# LockSequencer.net
KiCad netlist of a schematic drawn in EAGLE
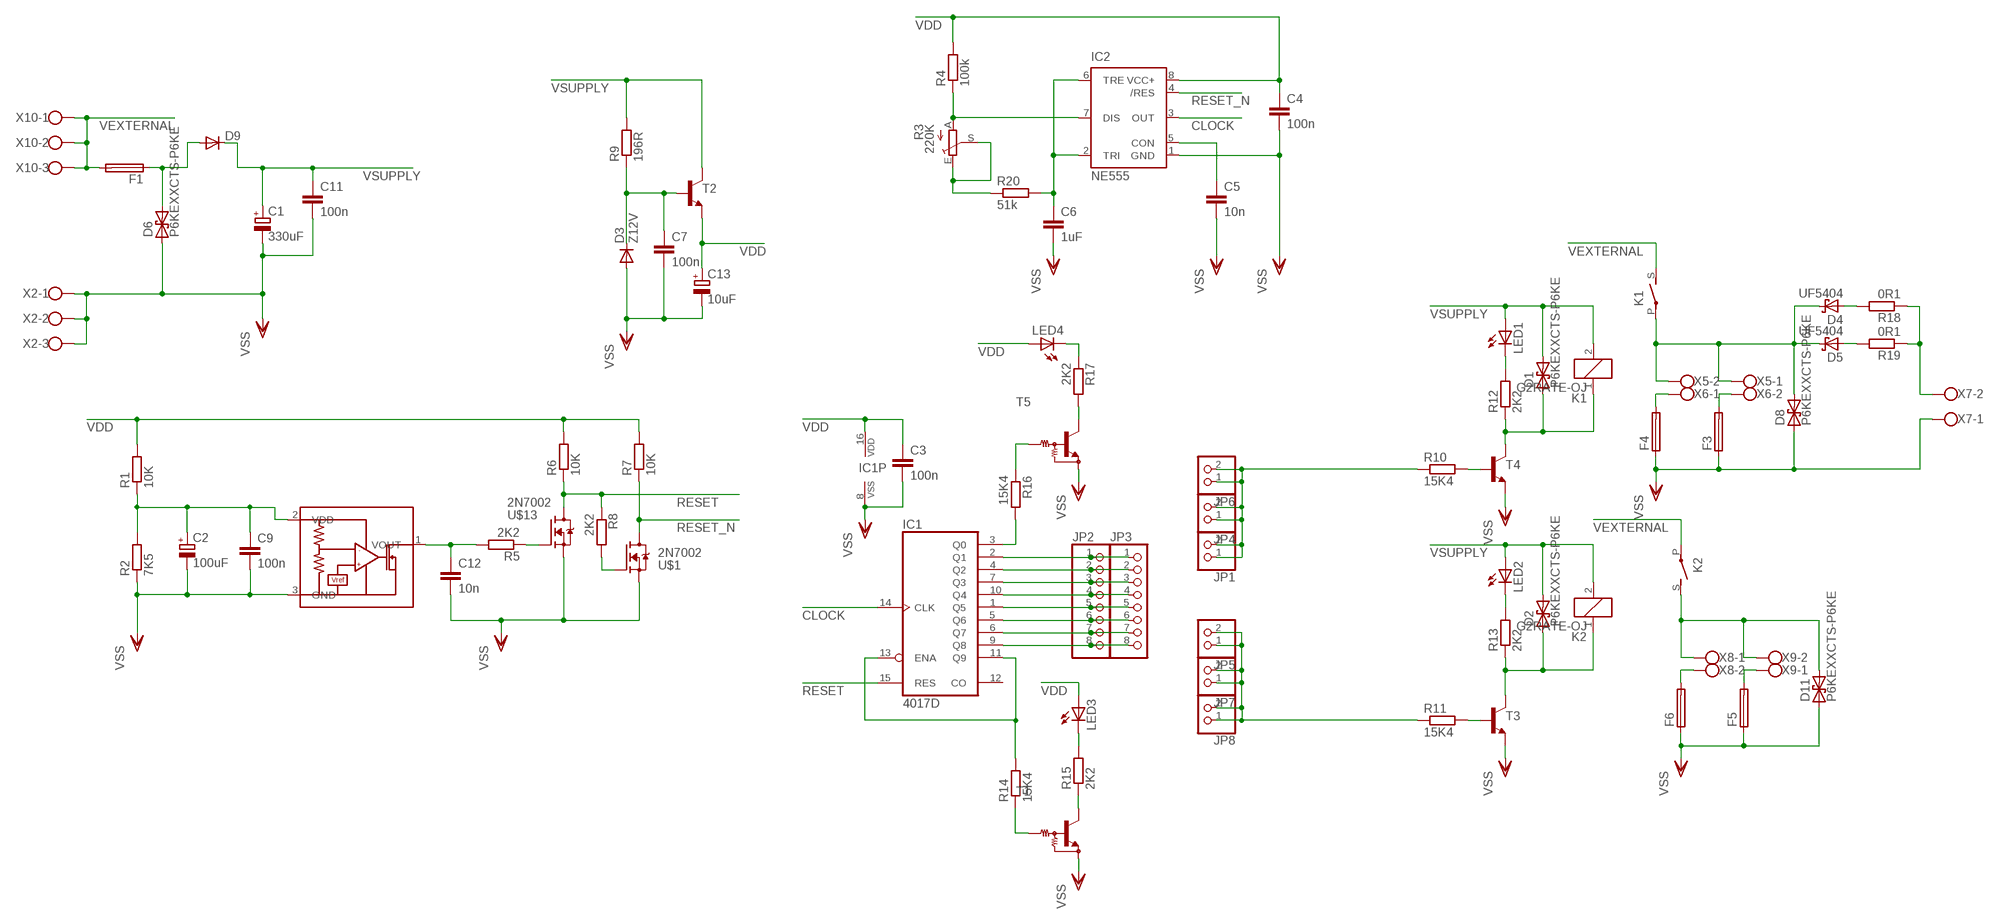
[diagram p0: schematic, sheet 1]

(export (version "E")
  (design (tool "Eeschema 10.0.6"))
  (components
    (comp (ref "C1")
      (value "330uF")
      (footprint "eagle-import:E3,5-8")
      (libsource (lib "eagle-import") (part "CPOL-EUE3.5-8"))
    )
    (comp (ref "C2")
      (value "100uF")
      (footprint "eagle-import:E2-5")
      (libsource (lib "eagle-import") (part "CPOL-EUE2-5"))
    )
    (comp (ref "C3")
      (value "100n")
      (footprint "eagle-import:C1206K")
      (libsource (lib "eagle-import") (part "C-EUC1206K"))
    )
    (comp (ref "C4")
      (value "100n")
      (footprint "eagle-import:C050-024X044")
      (libsource (lib "eagle-import") (part "C-EU050-024X044"))
    )
    (comp (ref "C5")
      (value "10n")
      (footprint "eagle-import:C1206K")
      (libsource (lib "eagle-import") (part "C-EUC1206K"))
    )
    (comp (ref "C6")
      (value "1uF")
      (footprint "eagle-import:C1206K")
      (libsource (lib "eagle-import") (part "C-EUC1206K"))
    )
    (comp (ref "C7")
      (value "100n")
      (footprint "eagle-import:C1206K")
      (libsource (lib "eagle-import") (part "C-EUC1206K"))
    )
    (comp (ref "C9")
      (value "100n")
      (footprint "eagle-import:C1206K")
      (libsource (lib "eagle-import") (part "C-EUC1206K"))
    )
    (comp (ref "C11")
      (value "100n")
      (footprint "eagle-import:C050-024X044")
      (libsource (lib "eagle-import") (part "C-EU050-024X044"))
    )
    (comp (ref "C12")
      (value "10n")
      (footprint "eagle-import:C1206K")
      (libsource (lib "eagle-import") (part "C-EUC1206K"))
    )
    (comp (ref "C13")
      (value "10uF")
      (footprint "eagle-import:E2-5")
      (libsource (lib "eagle-import") (part "CPOL-EUE2-5"))
    )
    (comp (ref "D1")
      (value "P6KEXXCTS-P6KE")
      (footprint "eagle-import:DO15-10")
      (libsource (lib "eagle-import") (part "P6KEXXCTS-P6KE"))
    )
    (comp (ref "D2")
      (value "P6KEXXCTS-P6KE")
      (footprint "eagle-import:DO15-10")
      (libsource (lib "eagle-import") (part "P6KEXXCTS-P6KE"))
    )
    (comp (ref "D3")
      (value "Z12V")
      (footprint "eagle-import:SOD323-W")
      (libsource (lib "eagle-import") (part "DIODE-SOD323-W"))
    )
    (comp (ref "D4")
      (value "UF5404")
      (footprint "eagle-import:CB429-15R")
      (libsource (lib "eagle-import") (part "SCHOTTKY-DIODECB429-15VR"))
    )
    (comp (ref "D5")
      (value "UF5404")
      (footprint "eagle-import:CB429-15V")
      (libsource (lib "eagle-import") (part "SCHOTTKY-DIODECB429-15V"))
    )
    (comp (ref "D6")
      (value "P6KEXXCTS-P6KE")
      (footprint "eagle-import:DO15-10")
      (libsource (lib "eagle-import") (part "P6KEXXCTS-P6KE"))
    )
    (comp (ref "D8")
      (value "P6KEXXCTS-P6KE")
      (footprint "eagle-import:DO15-10")
      (libsource (lib "eagle-import") (part "P6KEXXCTS-P6KE"))
    )
    (comp (ref "D9")
      (value "DIODE-SOD123")
      (footprint "eagle-import:SOD123")
      (libsource (lib "eagle-import") (part "DIODE-SOD123"))
    )
    (comp (ref "D11")
      (value "P6KEXXCTS-P6KE")
      (footprint "eagle-import:DO15-10")
      (libsource (lib "eagle-import") (part "P6KEXXCTS-P6KE"))
    )
    (comp (ref "F1")
      (value "TE5")
      (footprint "eagle-import:TE5")
      (libsource (lib "eagle-import") (part "TE5"))
    )
    (comp (ref "F3")
      (value "TE5")
      (footprint "eagle-import:TE5")
      (libsource (lib "eagle-import") (part "TE5"))
    )
    (comp (ref "F4")
      (value "TE5")
      (footprint "eagle-import:TE5")
      (libsource (lib "eagle-import") (part "TE5"))
    )
    (comp (ref "F5")
      (value "TE5")
      (footprint "eagle-import:TE5")
      (libsource (lib "eagle-import") (part "TE5"))
    )
    (comp (ref "F6")
      (value "TE5")
      (footprint "eagle-import:TE5")
      (libsource (lib "eagle-import") (part "TE5"))
    )
    (comp (ref "IC1")
      (value "4017D")
      (footprint "eagle-import:SO16")
      (libsource (lib "eagle-import") (part "4017D"))
    )
    (comp (ref "IC2")
      (value "NE555")
      (footprint "eagle-import:DIL-08")
      (fields (field (name "MF") "Arrow Electronics") (field (name "MPN") "NE555N"))
      (libsource (lib "eagle-import") (part "NE555"))
    )
    (comp (ref "JP1")
      (value "PINHD-1X2")
      (footprint "eagle-import:1X02")
      (libsource (lib "eagle-import") (part "PINHD-1X2"))
    )
    (comp (ref "JP2")
      (value "PINHD-1X8")
      (footprint "eagle-import:1X08")
      (libsource (lib "eagle-import") (part "PINHD-1X8"))
    )
    (comp (ref "JP3")
      (value "PINHD-1X8")
      (footprint "eagle-import:1X08")
      (libsource (lib "eagle-import") (part "PINHD-1X8"))
    )
    (comp (ref "JP4")
      (value "PINHD-1X2")
      (footprint "eagle-import:1X02")
      (libsource (lib "eagle-import") (part "PINHD-1X2"))
    )
    (comp (ref "JP5")
      (value "PINHD-1X2")
      (footprint "eagle-import:1X02")
      (libsource (lib "eagle-import") (part "PINHD-1X2"))
    )
    (comp (ref "JP6")
      (value "PINHD-1X2")
      (footprint "eagle-import:1X02")
      (libsource (lib "eagle-import") (part "PINHD-1X2"))
    )
    (comp (ref "JP7")
      (value "PINHD-1X2")
      (footprint "eagle-import:1X02")
      (libsource (lib "eagle-import") (part "PINHD-1X2"))
    )
    (comp (ref "JP8")
      (value "PINHD-1X2")
      (footprint "eagle-import:1X02")
      (libsource (lib "eagle-import") (part "PINHD-1X2"))
    )
    (comp (ref "K1")
      (value "G2RATE-OJ")
      (footprint "eagle-import:G2RA-SHORTER")
      (libsource (lib "eagle-import") (part "G2RATE-OJ"))
    )
    (comp (ref "K2")
      (value "G2RATE-OJ")
      (footprint "eagle-import:G2RA-SHORTER")
      (libsource (lib "eagle-import") (part "G2RATE-OJ"))
    )
    (comp (ref "LED1")
      (value "LED5MM")
      (footprint "eagle-import:LED5MM")
      (libsource (lib "eagle-import") (part "LED5MM"))
    )
    (comp (ref "LED2")
      (value "LED5MM")
      (footprint "eagle-import:LED5MM")
      (libsource (lib "eagle-import") (part "LED5MM"))
    )
    (comp (ref "LED3")
      (value "LED5MM")
      (footprint "eagle-import:LED5MM")
      (libsource (lib "eagle-import") (part "LED5MM"))
    )
    (comp (ref "LED4")
      (value "LED5MM")
      (footprint "eagle-import:LED5MM")
      (libsource (lib "eagle-import") (part "LED5MM"))
    )
    (comp (ref "R1")
      (value "10K")
      (footprint "eagle-import:0207_7")
      (libsource (lib "eagle-import") (part "R-EU_0207/7"))
    )
    (comp (ref "R2")
      (value "7K5")
      (footprint "eagle-import:0207_7")
      (libsource (lib "eagle-import") (part "R-EU_0207/7"))
    )
    (comp (ref "R3")
      (value "220K")
      (footprint "eagle-import:CA9V")
      (libsource (lib "eagle-import") (part "TRIM_EU-CA9V"))
    )
    (comp (ref "R4")
      (value "100k")
      (footprint "eagle-import:0207_7")
      (libsource (lib "eagle-import") (part "R-EU_0207/7"))
    )
    (comp (ref "R5")
      (value "2K2")
      (footprint "eagle-import:R0402")
      (libsource (lib "eagle-import") (part "R-EU_R0402"))
    )
    (comp (ref "R6")
      (value "10K")
      (footprint "eagle-import:0207_7")
      (libsource (lib "eagle-import") (part "R-EU_0207/7"))
    )
    (comp (ref "R7")
      (value "10K")
      (footprint "eagle-import:R0805")
      (libsource (lib "eagle-import") (part "R-EU_R0805"))
    )
    (comp (ref "R8")
      (value "2K2")
      (footprint "eagle-import:0207_7")
      (libsource (lib "eagle-import") (part "R-EU_0207/7"))
    )
    (comp (ref "R9")
      (value "196R")
      (footprint "eagle-import:R0805")
      (libsource (lib "eagle-import") (part "R-EU_R0805"))
    )
    (comp (ref "R10")
      (value "15K4")
      (footprint "eagle-import:R0603")
      (libsource (lib "eagle-import") (part "R-EU_R0603"))
    )
    (comp (ref "R11")
      (value "15K4")
      (footprint "eagle-import:R0603")
      (libsource (lib "eagle-import") (part "R-EU_R0603"))
    )
    (comp (ref "R12")
      (value "2K2")
      (footprint "eagle-import:0207_7")
      (libsource (lib "eagle-import") (part "R-EU_0207/7"))
    )
    (comp (ref "R13")
      (value "2K2")
      (footprint "eagle-import:0207_7")
      (libsource (lib "eagle-import") (part "R-EU_0207/7"))
    )
    (comp (ref "R14")
      (value "15K4")
      (footprint "eagle-import:R0603")
      (libsource (lib "eagle-import") (part "R-EU_R0603"))
    )
    (comp (ref "R15")
      (value "2K2")
      (footprint "eagle-import:0207_7")
      (libsource (lib "eagle-import") (part "R-EU_0207/7"))
    )
    (comp (ref "R16")
      (value "15K4")
      (footprint "eagle-import:R0603")
      (libsource (lib "eagle-import") (part "R-EU_R0603"))
    )
    (comp (ref "R17")
      (value "2K2")
      (footprint "eagle-import:0207_7")
      (libsource (lib "eagle-import") (part "R-EU_0207/7"))
    )
    (comp (ref "R18")
      (value "0R1")
      (footprint "eagle-import:R2512")
      (libsource (lib "eagle-import") (part "R-EU_R2512"))
    )
    (comp (ref "R19")
      (value "0R1")
      (footprint "eagle-import:R2512")
      (libsource (lib "eagle-import") (part "R-EU_R2512"))
    )
    (comp (ref "R20")
      (value "51k")
      (footprint "eagle-import:0207_7")
      (libsource (lib "eagle-import") (part "R-EU_0207/7"))
    )
    (comp (ref "T1")
      (value "-NPN_DRIVER-")
      (footprint "eagle-import:SOT23")
      (libsource (lib "eagle-import") (part "-NPN_DRIVER-"))
    )
    (comp (ref "T2")
      (value "MMBTA42LT1-NPN-SOT23-BEC")
      (footprint "eagle-import:SOT23-BEC")
      (libsource (lib "eagle-import") (part "-NPN-SOT23-BECMMBTA42LT1"))
    )
    (comp (ref "T3")
      (value "MMBTA42LT1-NPN-SOT23-BEC")
      (footprint "eagle-import:SOT23-BEC")
      (libsource (lib "eagle-import") (part "-NPN-SOT23-BECMMBTA42LT1"))
    )
    (comp (ref "T4")
      (value "MMBTA42LT1-NPN-SOT23-BEC")
      (footprint "eagle-import:SOT23-BEC")
      (libsource (lib "eagle-import") (part "-NPN-SOT23-BECMMBTA42LT1"))
    )
    (comp (ref "T5")
      (value "-NPN_DRIVER-")
      (footprint "eagle-import:SOT23")
      (libsource (lib "eagle-import") (part "-NPN_DRIVER-"))
    )
    (comp (ref "U$1")
      (value "2N7002")
      (footprint "eagle-import:SOT23")
      (libsource (lib "eagle-import") (part "2N7002"))
    )
    (comp (ref "U$4")
      (value "BU48XXG")
      (footprint "eagle-import:SOT95P280X125-5N")
      (libsource (lib "eagle-import") (part "BU48XXG"))
    )
    (comp (ref "U$13")
      (value "2N7002")
      (footprint "eagle-import:SOT23")
      (libsource (lib "eagle-import") (part "2N7002"))
    )
    (comp (ref "X2")
      (value "W237-103")
      (footprint "eagle-import:W237-103")
      (fields (field (name "MPN") "237-103"))
      (libsource (lib "eagle-import") (part "W237-103"))
    )
    (comp (ref "X5")
      (value "W237-102")
      (footprint "eagle-import:W237-102")
      (fields (field (name "MPN") "237-102"))
      (libsource (lib "eagle-import") (part "W237-102"))
    )
    (comp (ref "X6")
      (value "W237-102")
      (footprint "eagle-import:W237-102")
      (fields (field (name "MPN") "237-102"))
      (libsource (lib "eagle-import") (part "W237-102"))
    )
    (comp (ref "X7")
      (value "W237-102")
      (footprint "eagle-import:W237-102")
      (fields (field (name "MPN") "237-102"))
      (libsource (lib "eagle-import") (part "W237-102"))
    )
    (comp (ref "X8")
      (value "W237-102")
      (footprint "eagle-import:W237-102")
      (fields (field (name "MPN") "237-102"))
      (libsource (lib "eagle-import") (part "W237-102"))
    )
    (comp (ref "X9")
      (value "W237-102")
      (footprint "eagle-import:W237-102")
      (fields (field (name "MPN") "237-102"))
      (libsource (lib "eagle-import") (part "W237-102"))
    )
    (comp (ref "X10")
      (value "W237-103")
      (footprint "eagle-import:W237-103")
      (fields (field (name "MPN") "237-103"))
      (libsource (lib "eagle-import") (part "W237-103"))
    )
  )
  (nets
    (net (code "1") (name "/CLOCK") (class "Default")
      (node (ref "IC1") (pin "14") (pinfunction "CLK_14") (pintype "input"))
      (node (ref "IC2") (pin "3") (pinfunction "OUT_3") (pintype "output"))
    )
    (net (code "2") (name "/RESET") (class "Default")
      (node (ref "IC1") (pin "15") (pinfunction "RES_15") (pintype "input"))
      (node (ref "R6") (pin "1") (pinfunction "1_1") (pintype "passive"))
      (node (ref "R8") (pin "1") (pinfunction "1_1") (pintype "passive"))
      (node (ref "U$13") (pin "3") (pinfunction "D_3") (pintype "passive"))
    )
    (net (code "3") (name "/RESET_N") (class "Default")
      (node (ref "IC2") (pin "4") (pinfunction "/RES_4") (pintype "input"))
      (node (ref "R7") (pin "1") (pinfunction "1_1") (pintype "passive"))
      (node (ref "U$1") (pin "3") (pinfunction "D_3") (pintype "passive"))
    )
    (net (code "4") (name "/VDD") (class "Default")
      (node (ref "C13") (pin "+") (pinfunction "+_+") (pintype "passive"))
      (node (ref "C3") (pin "1") (pinfunction "1_1") (pintype "passive"))
      (node (ref "C4") (pin "1") (pinfunction "1_1") (pintype "passive"))
      (node (ref "IC1") (pin "16") (pinfunction "VDD_16") (pintype "power_in"))
      (node (ref "IC2") (pin "8") (pinfunction "VCC+_8") (pintype "power_in"))
      (node (ref "LED3") (pin "A") (pinfunction "A_A") (pintype "passive"))
      (node (ref "LED4") (pin "A") (pinfunction "A_A") (pintype "passive"))
      (node (ref "R1") (pin "2") (pinfunction "2_2") (pintype "passive"))
      (node (ref "R4") (pin "2") (pinfunction "2_2") (pintype "passive"))
      (node (ref "R6") (pin "2") (pinfunction "2_2") (pintype "passive"))
      (node (ref "R7") (pin "2") (pinfunction "2_2") (pintype "passive"))
      (node (ref "T2") (pin "E") (pinfunction "E_E") (pintype "passive"))
    )
    (net (code "5") (name "/VEXTERNAL") (class "Default")
      (node (ref "F1") (pin "2") (pinfunction "2_2") (pintype "passive"))
      (node (ref "K1") (pin "S") (pinfunction "S_S") (pintype "passive"))
      (node (ref "K2") (pin "P") (pinfunction "P_P") (pintype "passive"))
      (node (ref "X10") (pin "1") (pinfunction "KL_1") (pintype "passive"))
      (node (ref "X10") (pin "2") (pinfunction "KL_2") (pintype "passive"))
      (node (ref "X10") (pin "3") (pinfunction "KL_3") (pintype "passive"))
    )
    (net (code "6") (name "/VSUPPLY") (class "Default")
      (node (ref "C1") (pin "+") (pinfunction "+_+") (pintype "passive"))
      (node (ref "C11") (pin "1") (pinfunction "1_1") (pintype "passive"))
      (node (ref "D1") (pin "C") (pinfunction "2_C") (pintype "passive"))
      (node (ref "D2") (pin "C") (pinfunction "2_C") (pintype "passive"))
      (node (ref "D9") (pin "C") (pinfunction "C_C") (pintype "passive"))
      (node (ref "K1") (pin "2") (pinfunction "2_2") (pintype "passive"))
      (node (ref "K2") (pin "2") (pinfunction "2_2") (pintype "passive"))
      (node (ref "LED1") (pin "A") (pinfunction "A_A") (pintype "passive"))
      (node (ref "LED2") (pin "A") (pinfunction "A_A") (pintype "passive"))
      (node (ref "R9") (pin "2") (pinfunction "2_2") (pintype "passive"))
      (node (ref "T2") (pin "C") (pinfunction "C_C") (pintype "passive"))
    )
    (net (code "7") (name "Net-(C7-Pad1)") (class "Default")
      (node (ref "C7") (pin "1") (pinfunction "1_1") (pintype "passive"))
      (node (ref "D3") (pin "C") (pinfunction "C_C") (pintype "passive"))
      (node (ref "R9") (pin "1") (pinfunction "1_1") (pintype "passive"))
      (node (ref "T2") (pin "B") (pinfunction "B_B") (pintype "passive"))
    )
    (net (code "8") (name "Net-(D1-1)") (class "Default")
      (node (ref "D1") (pin "A") (pinfunction "1_A") (pintype "passive"))
      (node (ref "K1") (pin "1") (pinfunction "1_1") (pintype "passive"))
      (node (ref "R12") (pin "1") (pinfunction "1_1") (pintype "passive"))
      (node (ref "T4") (pin "C") (pinfunction "C_C") (pintype "passive"))
    )
    (net (code "9") (name "Net-(D2-1)") (class "Default")
      (node (ref "D2") (pin "A") (pinfunction "1_A") (pintype "passive"))
      (node (ref "K2") (pin "1") (pinfunction "1_1") (pintype "passive"))
      (node (ref "R13") (pin "1") (pinfunction "1_1") (pintype "passive"))
      (node (ref "T3") (pin "C") (pinfunction "C_C") (pintype "passive"))
    )
    (net (code "10") (name "Net-(D4-PadA)") (class "Default")
      (node (ref "D4") (pin "A") (pinfunction "A_A") (pintype "passive"))
      (node (ref "R18") (pin "2") (pinfunction "2_2") (pintype "passive"))
    )
    (net (code "11") (name "Net-(D5-PadA)") (class "Default")
      (node (ref "D5") (pin "A") (pinfunction "A_A") (pintype "passive"))
      (node (ref "R19") (pin "2") (pinfunction "2_2") (pintype "passive"))
    )
    (net (code "12") (name "Net-(D6-2)") (class "Default")
      (node (ref "D6") (pin "C") (pinfunction "2_C") (pintype "passive"))
      (node (ref "D9") (pin "A") (pinfunction "A_A") (pintype "passive"))
      (node (ref "F1") (pin "1") (pinfunction "1_1") (pintype "passive"))
    )
    (net (code "13") (name "Net-(D8-2)") (class "Default")
      (node (ref "D4") (pin "C") (pinfunction "C_C") (pintype "passive"))
      (node (ref "D5") (pin "C") (pinfunction "C_C") (pintype "passive"))
      (node (ref "D8") (pin "C") (pinfunction "2_C") (pintype "passive"))
      (node (ref "K1") (pin "P") (pinfunction "P_P") (pintype "passive"))
      (node (ref "X5") (pin "1") (pinfunction "KL_1") (pintype "passive"))
      (node (ref "X5") (pin "2") (pinfunction "KL_2") (pintype "passive"))
    )
    (net (code "14") (name "Net-(D11-2)") (class "Default")
      (node (ref "D11") (pin "C") (pinfunction "2_C") (pintype "passive"))
      (node (ref "K2") (pin "S") (pinfunction "S_S") (pintype "passive"))
      (node (ref "X8") (pin "1") (pinfunction "KL_1") (pintype "passive"))
      (node (ref "X9") (pin "2") (pinfunction "KL_2") (pintype "passive"))
    )
    (net (code "15") (name "Net-(IC1A-ENA)") (class "Default")
      (node (ref "IC1") (pin "11") (pinfunction "Q9_11") (pintype "output"))
      (node (ref "IC1") (pin "13") (pinfunction "ENA_13") (pintype "input"))
      (node (ref "R14") (pin "2") (pinfunction "2_2") (pintype "passive"))
    )
    (net (code "16") (name "Net-(IC1A-Q0)") (class "Default")
      (node (ref "IC1") (pin "3") (pinfunction "Q0_3") (pintype "output"))
      (node (ref "R16") (pin "2") (pinfunction "2_2") (pintype "passive"))
    )
    (net (code "17") (name "Net-(IC1A-Q1)") (class "Default")
      (node (ref "IC1") (pin "2") (pinfunction "Q1_2") (pintype "output"))
      (node (ref "JP2") (pin "1") (pinfunction "1_1") (pintype "passive"))
      (node (ref "JP3") (pin "1") (pinfunction "1_1") (pintype "passive"))
    )
    (net (code "18") (name "Net-(IC1A-Q2)") (class "Default")
      (node (ref "IC1") (pin "4") (pinfunction "Q2_4") (pintype "output"))
      (node (ref "JP2") (pin "2") (pinfunction "2_2") (pintype "passive"))
      (node (ref "JP3") (pin "2") (pinfunction "2_2") (pintype "passive"))
    )
    (net (code "19") (name "Net-(IC1A-Q3)") (class "Default")
      (node (ref "IC1") (pin "7") (pinfunction "Q3_7") (pintype "output"))
      (node (ref "JP2") (pin "3") (pinfunction "3_3") (pintype "passive"))
      (node (ref "JP3") (pin "3") (pinfunction "3_3") (pintype "passive"))
    )
    (net (code "20") (name "Net-(IC1A-Q4)") (class "Default")
      (node (ref "IC1") (pin "10") (pinfunction "Q4_10") (pintype "output"))
      (node (ref "JP2") (pin "4") (pinfunction "4_4") (pintype "passive"))
      (node (ref "JP3") (pin "4") (pinfunction "4_4") (pintype "passive"))
    )
    (net (code "21") (name "Net-(IC1A-Q5)") (class "Default")
      (node (ref "IC1") (pin "1") (pinfunction "Q5_1") (pintype "output"))
      (node (ref "JP2") (pin "5") (pinfunction "5_5") (pintype "passive"))
      (node (ref "JP3") (pin "5") (pinfunction "5_5") (pintype "passive"))
    )
    (net (code "22") (name "Net-(IC1A-Q6)") (class "Default")
      (node (ref "IC1") (pin "5") (pinfunction "Q6_5") (pintype "output"))
      (node (ref "JP2") (pin "6") (pinfunction "6_6") (pintype "passive"))
      (node (ref "JP3") (pin "6") (pinfunction "6_6") (pintype "passive"))
    )
    (net (code "23") (name "Net-(IC1A-Q7)") (class "Default")
      (node (ref "IC1") (pin "6") (pinfunction "Q7_6") (pintype "output"))
      (node (ref "JP2") (pin "7") (pinfunction "7_7") (pintype "passive"))
      (node (ref "JP3") (pin "7") (pinfunction "7_7") (pintype "passive"))
    )
    (net (code "24") (name "Net-(IC1A-Q8)") (class "Default")
      (node (ref "IC1") (pin "9") (pinfunction "Q8_9") (pintype "output"))
      (node (ref "JP2") (pin "8") (pinfunction "8_8") (pintype "passive"))
      (node (ref "JP3") (pin "8") (pinfunction "8_8") (pintype "passive"))
    )
    (net (code "25") (name "Net-(IC2-CON)") (class "Default")
      (node (ref "C5") (pin "1") (pinfunction "1_1") (pintype "passive"))
      (node (ref "IC2") (pin "5") (pinfunction "CON_5") (pintype "input"))
    )
    (net (code "26") (name "Net-(IC2-DIS)") (class "Default")
      (node (ref "IC2") (pin "7") (pinfunction "DIS_7") (pintype "input"))
      (node (ref "R3") (pin "A") (pinfunction "A_A") (pintype "passive"))
      (node (ref "R4") (pin "1") (pinfunction "1_1") (pintype "passive"))
    )
    (net (code "27") (name "Net-(IC2-TRE)") (class "Default")
      (node (ref "C6") (pin "1") (pinfunction "1_1") (pintype "passive"))
      (node (ref "IC2") (pin "2") (pinfunction "TRI_2") (pintype "input"))
      (node (ref "IC2") (pin "6") (pinfunction "TRE_6") (pintype "input"))
      (node (ref "R20") (pin "2") (pinfunction "2_2") (pintype "passive"))
    )
    (net (code "28") (name "Net-(JP1-Pad1)") (class "Default")
      (node (ref "JP1") (pin "1") (pinfunction "1_1") (pintype "passive"))
      (node (ref "JP1") (pin "2") (pinfunction "2_2") (pintype "passive"))
      (node (ref "JP4") (pin "1") (pinfunction "1_1") (pintype "passive"))
      (node (ref "JP4") (pin "2") (pinfunction "2_2") (pintype "passive"))
      (node (ref "JP6") (pin "1") (pinfunction "1_1") (pintype "passive"))
      (node (ref "JP6") (pin "2") (pinfunction "2_2") (pintype "passive"))
      (node (ref "R10") (pin "1") (pinfunction "1_1") (pintype "passive"))
    )
    (net (code "29") (name "Net-(JP5-Pad1)") (class "Default")
      (node (ref "JP5") (pin "1") (pinfunction "1_1") (pintype "passive"))
      (node (ref "JP5") (pin "2") (pinfunction "2_2") (pintype "passive"))
      (node (ref "JP7") (pin "1") (pinfunction "1_1") (pintype "passive"))
      (node (ref "JP7") (pin "2") (pinfunction "2_2") (pintype "passive"))
      (node (ref "JP8") (pin "1") (pinfunction "1_1") (pintype "passive"))
      (node (ref "JP8") (pin "2") (pinfunction "2_2") (pintype "passive"))
      (node (ref "R11") (pin "1") (pinfunction "1_1") (pintype "passive"))
    )
    (net (code "30") (name "Net-(LED1-C)") (class "Default")
      (node (ref "LED1") (pin "K") (pinfunction "C_K") (pintype "passive"))
      (node (ref "R12") (pin "2") (pinfunction "2_2") (pintype "passive"))
    )
    (net (code "31") (name "Net-(LED2-C)") (class "Default")
      (node (ref "LED2") (pin "K") (pinfunction "C_K") (pintype "passive"))
      (node (ref "R13") (pin "2") (pinfunction "2_2") (pintype "passive"))
    )
    (net (code "32") (name "Net-(LED3-C)") (class "Default")
      (node (ref "LED3") (pin "K") (pinfunction "C_K") (pintype "passive"))
      (node (ref "R15") (pin "2") (pinfunction "2_2") (pintype "passive"))
    )
    (net (code "33") (name "Net-(LED4-C)") (class "Default")
      (node (ref "LED4") (pin "K") (pinfunction "C_K") (pintype "passive"))
      (node (ref "R17") (pin "1") (pinfunction "1_1") (pintype "passive"))
    )
    (net (code "34") (name "Net-(R10-Pad2)") (class "Default")
      (node (ref "R10") (pin "2") (pinfunction "2_2") (pintype "passive"))
      (node (ref "T4") (pin "B") (pinfunction "B_B") (pintype "passive"))
    )
    (net (code "35") (name "Net-(R11-Pad2)") (class "Default")
      (node (ref "R11") (pin "2") (pinfunction "2_2") (pintype "passive"))
      (node (ref "T3") (pin "B") (pinfunction "B_B") (pintype "passive"))
    )
    (net (code "36") (name "Net-(R20-Pad1)") (class "Default")
      (node (ref "R20") (pin "1") (pinfunction "1_1") (pintype "passive"))
      (node (ref "R3") (pin "E") (pinfunction "E_E") (pintype "passive"))
      (node (ref "R3") (pin "S") (pinfunction "S_S") (pintype "passive"))
    )
    (net (code "37") (name "Net-(T1-B)") (class "Default")
      (node (ref "R14") (pin "1") (pinfunction "1_1") (pintype "passive"))
      (node (ref "T1") (pin "1") (pinfunction "B_1") (pintype "passive"))
    )
    (net (code "38") (name "Net-(T1-C)") (class "Default")
      (node (ref "R15") (pin "1") (pinfunction "1_1") (pintype "passive"))
      (node (ref "T1") (pin "3") (pinfunction "C_3") (pintype "passive"))
    )
    (net (code "39") (name "Net-(T5-B)") (class "Default")
      (node (ref "R16") (pin "1") (pinfunction "1_1") (pintype "passive"))
      (node (ref "T5") (pin "1") (pinfunction "B_1") (pintype "passive"))
    )
    (net (code "40") (name "Net-(T5-C)") (class "Default")
      (node (ref "R17") (pin "2") (pinfunction "2_2") (pintype "passive"))
      (node (ref "T5") (pin "3") (pinfunction "C_3") (pintype "passive"))
    )
    (net (code "41") (name "Net-(U$1-G)") (class "Default")
      (node (ref "R8") (pin "2") (pinfunction "2_2") (pintype "passive"))
      (node (ref "U$1") (pin "1") (pinfunction "G_1") (pintype "passive"))
    )
    (net (code "42") (name "Net-(U$4-VDD)") (class "Default")
      (node (ref "C2") (pin "+") (pinfunction "+_+") (pintype "passive"))
      (node (ref "C9") (pin "1") (pinfunction "1_1") (pintype "passive"))
      (node (ref "R1") (pin "1") (pinfunction "1_1") (pintype "passive"))
      (node (ref "R2") (pin "2") (pinfunction "2_2") (pintype "passive"))
      (node (ref "U$4") (pin "2") (pinfunction "VDD_2") (pintype "bidirectional"))
    )
    (net (code "43") (name "Net-(U$4-VOUT)") (class "Default")
      (node (ref "C12") (pin "1") (pinfunction "1_1") (pintype "passive"))
      (node (ref "R5") (pin "2") (pinfunction "2_2") (pintype "passive"))
      (node (ref "U$4") (pin "1") (pinfunction "VOUT_1") (pintype "bidirectional"))
    )
    (net (code "44") (name "Net-(U$13-G)") (class "Default")
      (node (ref "R5") (pin "1") (pinfunction "1_1") (pintype "passive"))
      (node (ref "U$13") (pin "1") (pinfunction "G_1") (pintype "passive"))
    )
    (net (code "45") (name "Net-(X6A-KL)") (class "Default")
      (node (ref "F4") (pin "2") (pinfunction "2_2") (pintype "passive"))
      (node (ref "X6") (pin "1") (pinfunction "KL_1") (pintype "passive"))
    )
    (net (code "46") (name "Net-(X6B-KL)") (class "Default")
      (node (ref "F3") (pin "2") (pinfunction "2_2") (pintype "passive"))
      (node (ref "X6") (pin "2") (pinfunction "KL_2") (pintype "passive"))
    )
    (net (code "47") (name "Net-(X7B-KL)") (class "Default")
      (node (ref "R18") (pin "1") (pinfunction "1_1") (pintype "passive"))
      (node (ref "R19") (pin "1") (pinfunction "1_1") (pintype "passive"))
      (node (ref "X7") (pin "2") (pinfunction "KL_2") (pintype "passive"))
    )
    (net (code "48") (name "Net-(X8B-KL)") (class "Default")
      (node (ref "F6") (pin "2") (pinfunction "2_2") (pintype "passive"))
      (node (ref "X8") (pin "2") (pinfunction "KL_2") (pintype "passive"))
    )
    (net (code "49") (name "Net-(X9A-KL)") (class "Default")
      (node (ref "F5") (pin "2") (pinfunction "2_2") (pintype "passive"))
      (node (ref "X9") (pin "1") (pinfunction "KL_1") (pintype "passive"))
    )
    (net (code "50") (name "VSS") (class "Default")
      (node (ref "C1") (pin "-") (pinfunction "-_-") (pintype "passive"))
      (node (ref "C11") (pin "2") (pinfunction "2_2") (pintype "passive"))
      (node (ref "C12") (pin "2") (pinfunction "2_2") (pintype "passive"))
      (node (ref "C13") (pin "-") (pinfunction "-_-") (pintype "passive"))
      (node (ref "C2") (pin "-") (pinfunction "-_-") (pintype "passive"))
      (node (ref "C3") (pin "2") (pinfunction "2_2") (pintype "passive"))
      (node (ref "C4") (pin "2") (pinfunction "2_2") (pintype "passive"))
      (node (ref "C5") (pin "2") (pinfunction "2_2") (pintype "passive"))
      (node (ref "C6") (pin "2") (pinfunction "2_2") (pintype "passive"))
      (node (ref "C7") (pin "2") (pinfunction "2_2") (pintype "passive"))
      (node (ref "C9") (pin "2") (pinfunction "2_2") (pintype "passive"))
      (node (ref "D11") (pin "A") (pinfunction "1_A") (pintype "passive"))
      (node (ref "D3") (pin "A") (pinfunction "A_A") (pintype "passive"))
      (node (ref "D6") (pin "A") (pinfunction "1_A") (pintype "passive"))
      (node (ref "D8") (pin "A") (pinfunction "1_A") (pintype "passive"))
      (node (ref "F3") (pin "1") (pinfunction "1_1") (pintype "passive"))
      (node (ref "F4") (pin "1") (pinfunction "1_1") (pintype "passive"))
      (node (ref "F5") (pin "1") (pinfunction "1_1") (pintype "passive"))
      (node (ref "F6") (pin "1") (pinfunction "1_1") (pintype "passive"))
      (node (ref "IC1") (pin "8") (pinfunction "VSS_8") (pintype "power_in"))
      (node (ref "IC2") (pin "1") (pinfunction "GND_1") (pintype "power_in"))
      (node (ref "R2") (pin "1") (pinfunction "1_1") (pintype "passive"))
      (node (ref "T1") (pin "2") (pinfunction "E_2") (pintype "passive"))
      (node (ref "T3") (pin "E") (pinfunction "E_E") (pintype "passive"))
      (node (ref "T4") (pin "E") (pinfunction "E_E") (pintype "passive"))
      (node (ref "T5") (pin "2") (pinfunction "E_2") (pintype "passive"))
      (node (ref "U$1") (pin "2") (pinfunction "S_2") (pintype "passive"))
      (node (ref "U$13") (pin "2") (pinfunction "S_2") (pintype "passive"))
      (node (ref "U$4") (pin "3") (pinfunction "GND_3") (pintype "bidirectional"))
      (node (ref "X2") (pin "1") (pinfunction "KL_1") (pintype "passive"))
      (node (ref "X2") (pin "2") (pinfunction "KL_2") (pintype "passive"))
      (node (ref "X2") (pin "3") (pinfunction "KL_3") (pintype "passive"))
      (node (ref "X7") (pin "1") (pinfunction "KL_1") (pintype "passive"))
    )
    (net (code "51") (name "unconnected-(IC1A-CO-Pad12)") (class "Default")
      (node (ref "IC1") (pin "12") (pinfunction "CO_12") (pintype "output"))
    )
  )
)
